# CoopCommand-Control_Panel_2020-07-27_09-.net
KiCad netlist of a schematic drawn in EasyEDA
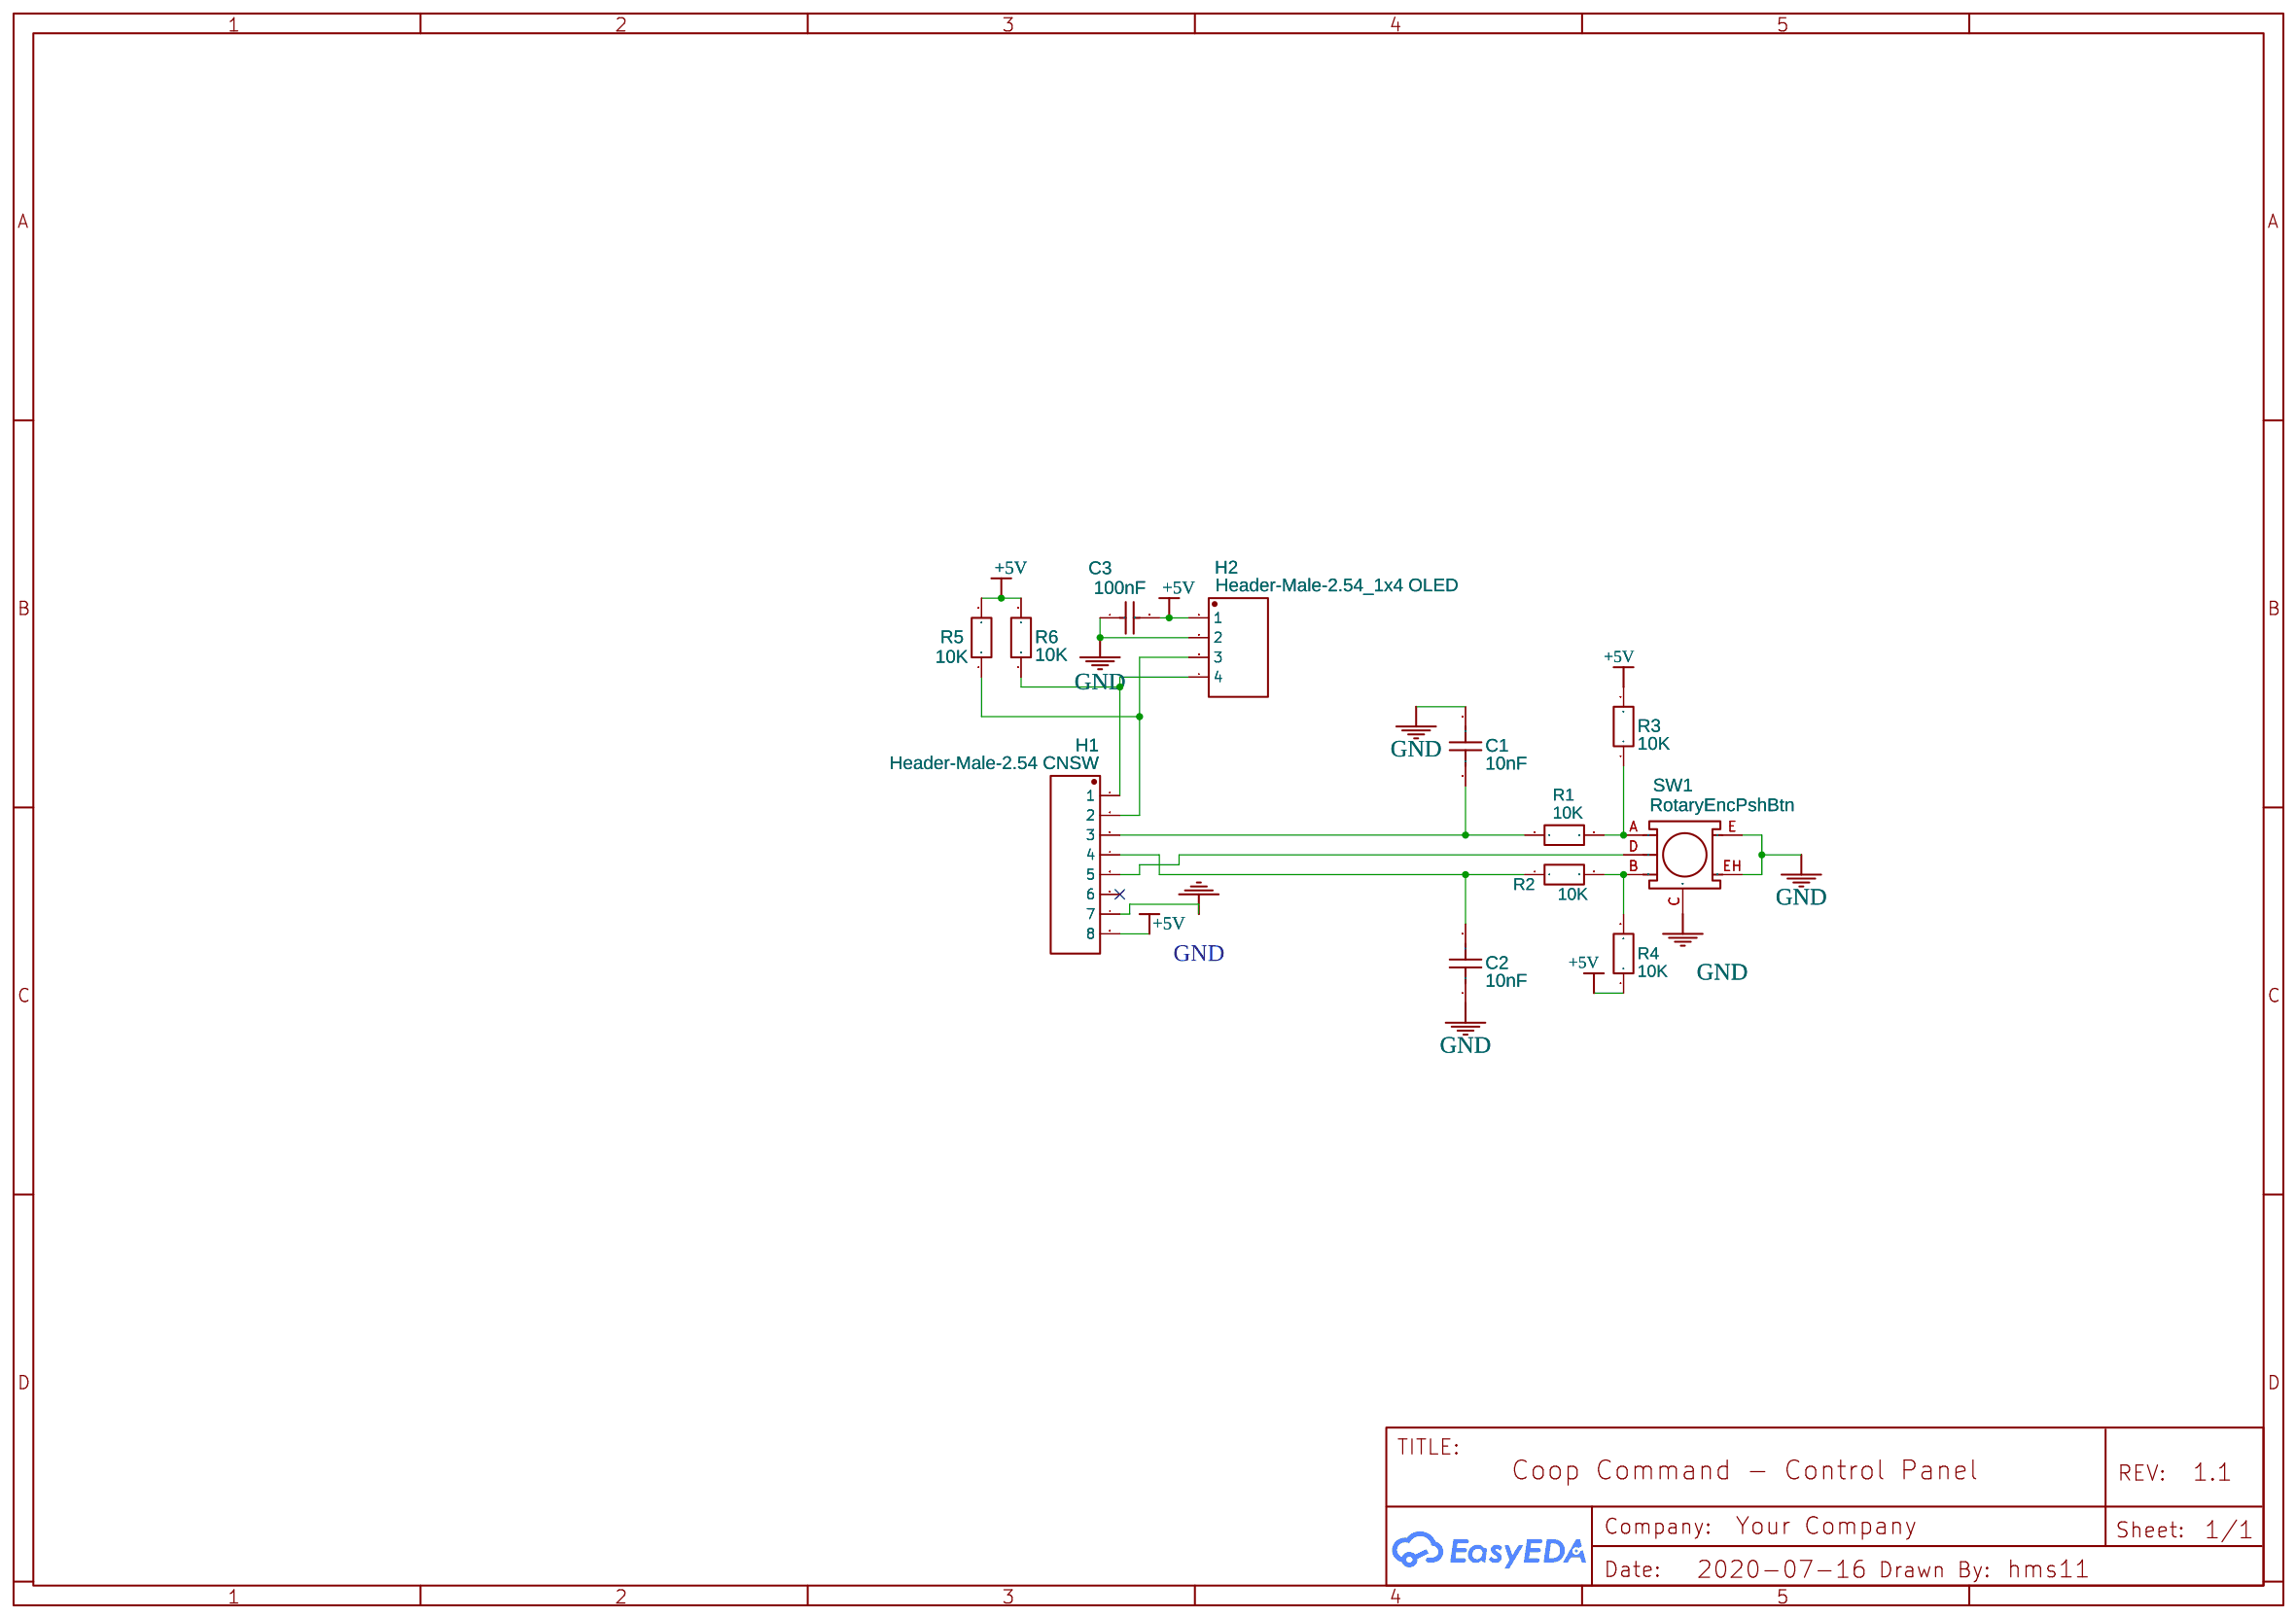
[diagram p0: schematic sheet]

(export (version "E")
  (design (tool "Eeschema 10.0.6"))
  (components
    (comp (ref "C1")
      (value "10nF")
      (fields
        (field (name "BOM_Manufacturer Part") "CC1H103ZA1AD3F4D10MF")
        (field (name "BOM_Supplier Part") "C254082")
      )
      (libsource (lib "") (part "CC1H103ZA1AD3F4D10MF"))
    )
    (comp (ref "C2")
      (value "10nF")
      (fields
        (field (name "BOM_Manufacturer Part") "CC1H103ZA1AD3F4D10MF")
        (field (name "BOM_Supplier Part") "C254082")
      )
      (libsource (lib "") (part "CC1H103ZA1AD3F4D10MF"))
    )
    (comp (ref "C3")
      (value "100nF")
      (fields
        (field (name "BOM_Manufacturer Part") "CS1F5.6Y5V1A104Z")
        (field (name "BOM_Supplier Part") "C9306")
      )
      (libsource (lib "") (part "CS1F5.6Y5V1A104Z"))
    )
    (comp (ref "H1")
      (value "Header-Male-2.54 CNSW")
      (fields
        (field (name "BOM_Manufacturer Part") "210S-1*8P L=11.6MMGold-plated black")
        (field (name "BOM_Supplier Part") "C124381")
      )
      (libsource (lib "") (part "Header-Male-2.54_1x8"))
    )
    (comp (ref "H2")
      (value "Header-Male-2.54_1x4 OLED")
      (fields
        (field (name "BOM_Manufacturer Part") "210S-1*4P L=11.6MMGold-plated black")
        (field (name "BOM_Supplier Part") "C124378")
      )
      (libsource (lib "") (part "Header-Male-2.54_1x4"))
    )
    (comp (ref "R1")
      (value "10K")
      (fields
        (field (name "BOM_Manufacturer Part") "RN 1/4W 10K F T/B A1")
        (field (name "BOM_Supplier Part") "C410695")
      )
      (libsource (lib "") (part "RN 1/4W 10K F T/B A1"))
    )
    (comp (ref "R2")
      (value "10K")
      (fields
        (field (name "BOM_Manufacturer Part") "RN 1/4W 10K F T/B A1")
        (field (name "BOM_Supplier Part") "C410695")
      )
      (libsource (lib "") (part "RN 1/4W 10K F T/B A1"))
    )
    (comp (ref "R3")
      (value "10K")
      (fields
        (field (name "BOM_Manufacturer Part") "RN 1/4W 10K F T/B A1")
        (field (name "BOM_Supplier Part") "C410695")
      )
      (libsource (lib "") (part "RN 1/4W 10K F T/B A1_1"))
    )
    (comp (ref "R4")
      (value "10K")
      (fields
        (field (name "BOM_Manufacturer Part") "RN 1/4W 10K F T/B A1")
        (field (name "BOM_Supplier Part") "C410695")
      )
      (libsource (lib "") (part "RN 1/4W 10K F T/B A1_1"))
    )
    (comp (ref "R5")
      (value "10K")
      (fields
        (field (name "BOM_Manufacturer Part") "RN 1/4W 10K F T/B A1")
        (field (name "BOM_Supplier Part") "C410695")
      )
      (libsource (lib "") (part "RN 1/4W 10K F T/B A1_1"))
    )
    (comp (ref "R6")
      (value "10K")
      (fields
        (field (name "BOM_Manufacturer Part") "RN 1/4W 10K F T/B A1")
        (field (name "BOM_Supplier Part") "C410695")
      )
      (libsource (lib "") (part "RN 1/4W 10K F T/B A1_1"))
    )
    (comp (ref "SW1")
      (value "RotaryEncPshBtn")
      (fields
        (field (name "BOM_Manufacturer Part") "EC11G1560414")
        (field (name "BOM_Supplier Part") "C470719")
      )
      (libsource (lib "") (part "EC11G1560414"))
    )
  )
  (nets
    (net (code "1") (name "+5V") (class "Default")
      (node (ref "C3") (pin "2") (pinfunction "2_2") (pintype "input"))
      (node (ref "H1") (pin "8") (pinfunction "8_8") (pintype "unspecified"))
      (node (ref "H2") (pin "1") (pinfunction "1_1") (pintype "unspecified"))
      (node (ref "R3") (pin "2") (pinfunction "2_2") (pintype "unspecified"))
      (node (ref "R4") (pin "1") (pinfunction "1_1") (pintype "unspecified"))
      (node (ref "R5") (pin "2") (pinfunction "2_2") (pintype "unspecified"))
      (node (ref "R6") (pin "2") (pinfunction "2_2") (pintype "unspecified"))
    )
    (net (code "2") (name "GND") (class "Default")
      (node (ref "C1") (pin "2") (pinfunction "2_2") (pintype "unspecified"))
      (node (ref "C2") (pin "1") (pinfunction "1_1") (pintype "unspecified"))
      (node (ref "C3") (pin "1") (pinfunction "1_1") (pintype "input"))
      (node (ref "H1") (pin "7") (pinfunction "7_7") (pintype "unspecified"))
      (node (ref "H2") (pin "2") (pinfunction "2_2") (pintype "unspecified"))
      (node (ref "SW1") (pin "C") (pinfunction "C_C") (pintype "unspecified"))
      (node (ref "SW1") (pin "E") (pinfunction "E_E") (pintype "unspecified"))
      (node (ref "SW1") (pin "EH") (pinfunction "EH_EH") (pintype "unspecified"))
    )
    (net (code "3") (name "Net-(C1-Pad1)") (class "Default")
      (node (ref "C1") (pin "1") (pinfunction "1_1") (pintype "unspecified"))
      (node (ref "H1") (pin "3") (pinfunction "3_3") (pintype "unspecified"))
      (node (ref "R1") (pin "1") (pinfunction "1_1") (pintype "unspecified"))
    )
    (net (code "4") (name "Net-(C2-Pad2)") (class "Default")
      (node (ref "C2") (pin "2") (pinfunction "2_2") (pintype "unspecified"))
      (node (ref "H1") (pin "4") (pinfunction "4_4") (pintype "unspecified"))
      (node (ref "R2") (pin "1") (pinfunction "1_1") (pintype "unspecified"))
    )
    (net (code "5") (name "Net-(H1-Pad1)") (class "Default")
      (node (ref "H1") (pin "1") (pinfunction "1_1") (pintype "unspecified"))
      (node (ref "H2") (pin "4") (pinfunction "4_4") (pintype "unspecified"))
      (node (ref "R6") (pin "1") (pinfunction "1_1") (pintype "unspecified"))
    )
    (net (code "6") (name "Net-(H1-Pad2)") (class "Default")
      (node (ref "H1") (pin "2") (pinfunction "2_2") (pintype "unspecified"))
      (node (ref "H2") (pin "3") (pinfunction "3_3") (pintype "unspecified"))
      (node (ref "R5") (pin "1") (pinfunction "1_1") (pintype "unspecified"))
    )
    (net (code "7") (name "Net-(H1-Pad5)") (class "Default")
      (node (ref "H1") (pin "5") (pinfunction "5_5") (pintype "unspecified"))
      (node (ref "SW1") (pin "D") (pinfunction "D_D") (pintype "unspecified"))
    )
    (net (code "8") (name "Net-(R1-Pad2)") (class "Default")
      (node (ref "R1") (pin "2") (pinfunction "2_2") (pintype "unspecified"))
      (node (ref "R3") (pin "1") (pinfunction "1_1") (pintype "unspecified"))
      (node (ref "SW1") (pin "A") (pinfunction "A_A") (pintype "unspecified"))
    )
    (net (code "9") (name "Net-(R2-Pad2)") (class "Default")
      (node (ref "R2") (pin "2") (pinfunction "2_2") (pintype "unspecified"))
      (node (ref "R4") (pin "2") (pinfunction "2_2") (pintype "unspecified"))
      (node (ref "SW1") (pin "B") (pinfunction "B_B") (pintype "unspecified"))
    )
    (net (code "10") (name "unconnected-(H1-Pad6)") (class "Default")
      (node (ref "H1") (pin "6") (pinfunction "6_6") (pintype "unspecified+no_connect"))
    )
  )
)
